# rotorsteuerung_create.net
KiCad netlist of a schematic drawn in EAGLE
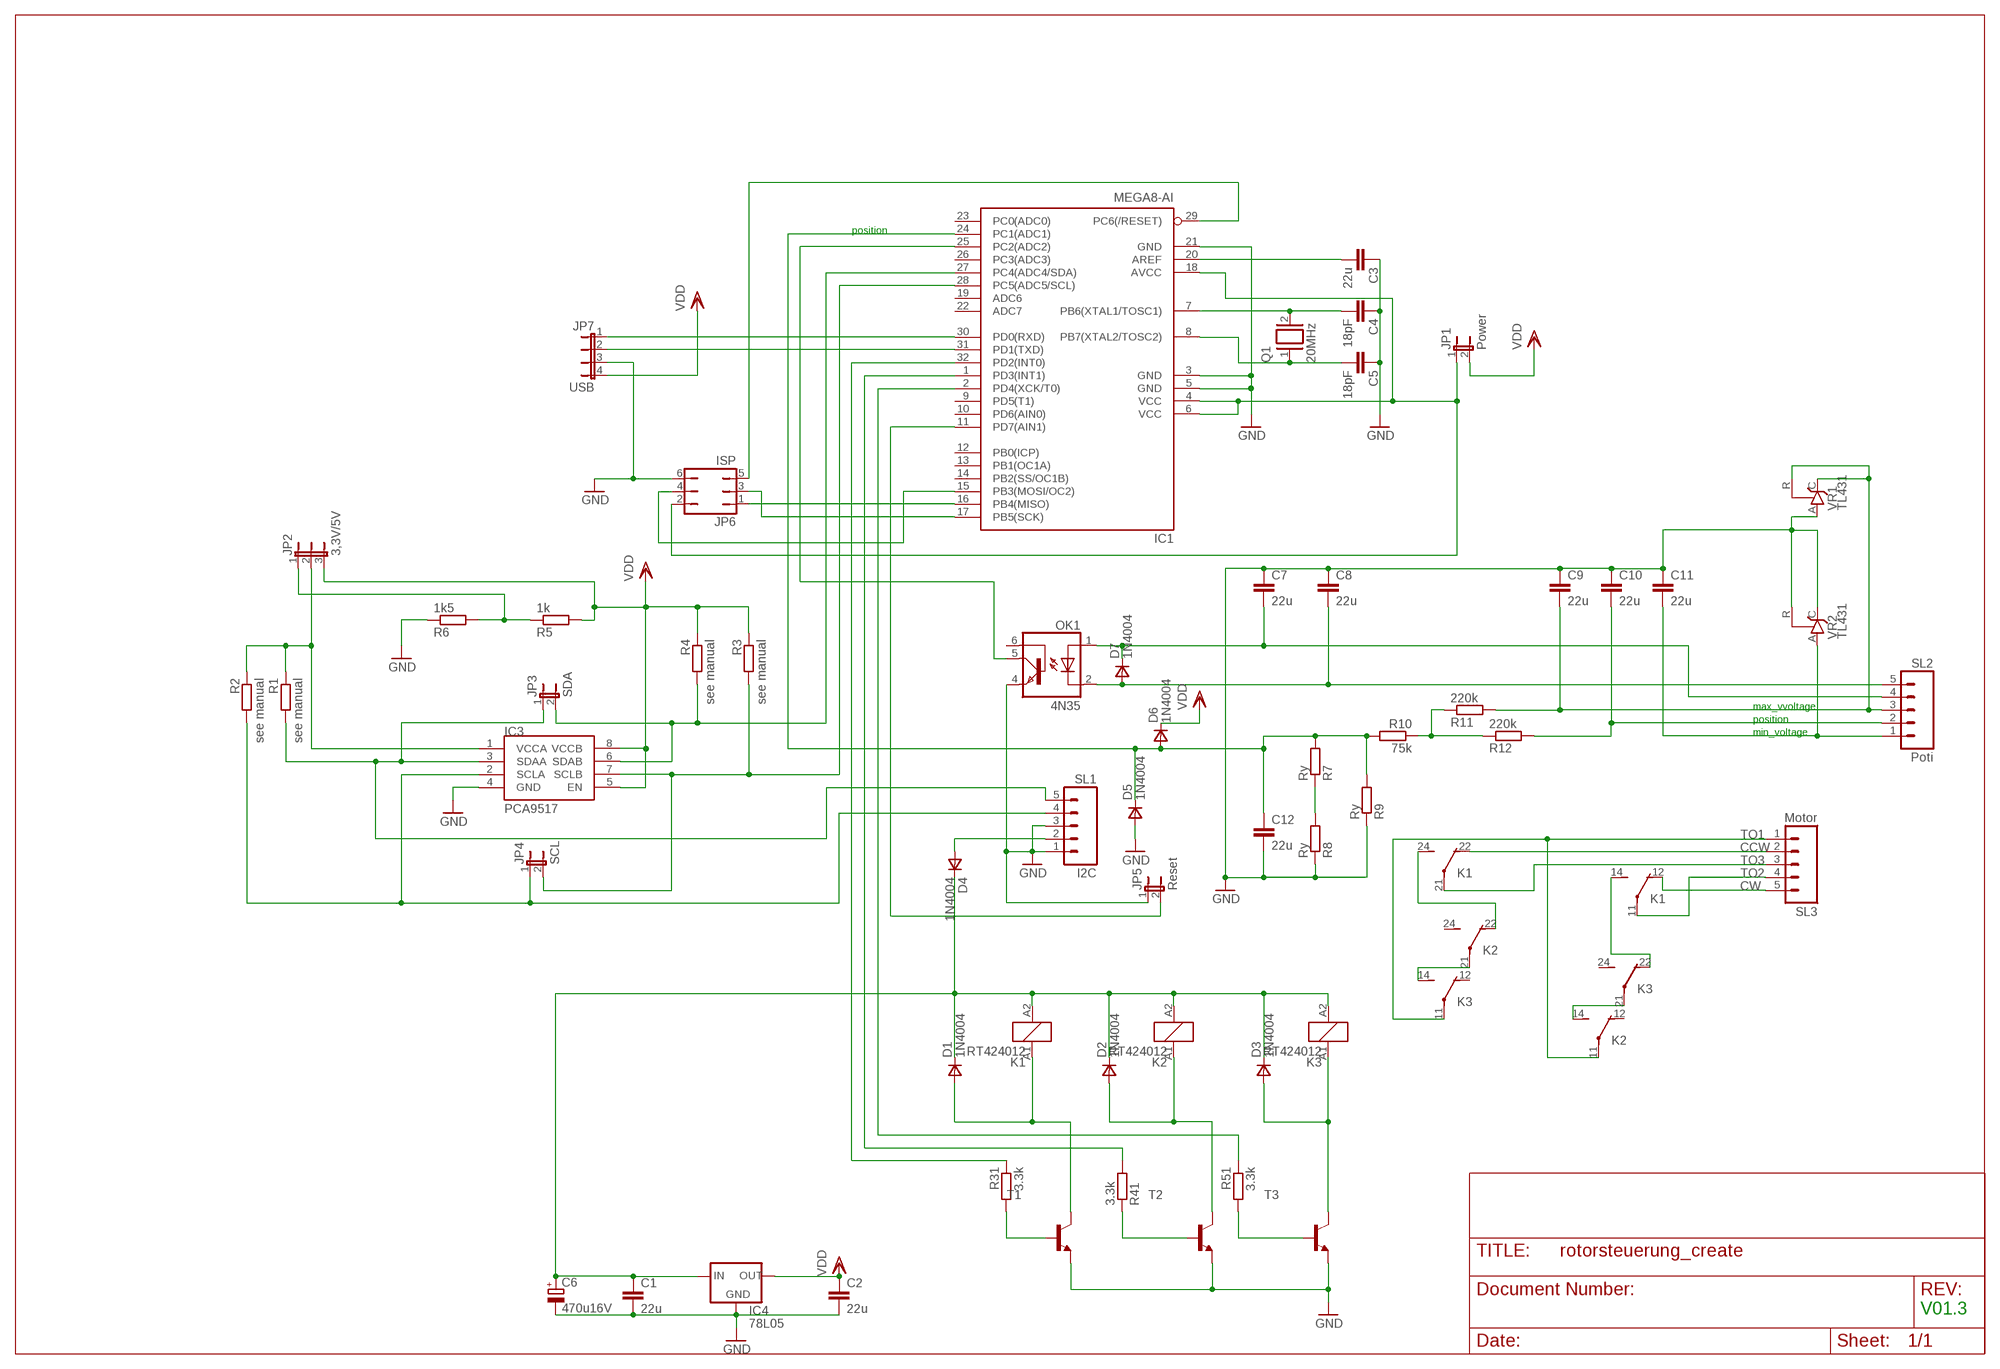
[diagram p0: schematic, sheet 1]

(export (version "E")
  (design (tool "Eeschema 10.0.6"))
  (components
    (comp (ref "C1")
      (value "22u")
      (footprint "eagle-import:C1206")
      (libsource (lib "eagle-import") (part "C-EUC1206"))
    )
    (comp (ref "C2")
      (value "22u")
      (footprint "eagle-import:C1206")
      (libsource (lib "eagle-import") (part "C-EUC1206"))
    )
    (comp (ref "C3")
      (value "22u")
      (footprint "eagle-import:C1206")
      (libsource (lib "eagle-import") (part "C-EUC1206"))
    )
    (comp (ref "C4")
      (value "18pF")
      (footprint "eagle-import:C025-024X044")
      (libsource (lib "eagle-import") (part "C-EU025-024X044"))
    )
    (comp (ref "C5")
      (value "18pF")
      (footprint "eagle-import:C025-024X044")
      (libsource (lib "eagle-import") (part "C-EU025-024X044"))
    )
    (comp (ref "C6")
      (value "470u16V")
      (footprint "eagle-import:E5-10,5")
      (libsource (lib "eagle-import") (part "CPOL-EUE5-10.5"))
    )
    (comp (ref "C7")
      (value "22u")
      (footprint "eagle-import:C1206")
      (libsource (lib "eagle-import") (part "C-EUC1206"))
    )
    (comp (ref "C8")
      (value "22u")
      (footprint "eagle-import:C1206")
      (libsource (lib "eagle-import") (part "C-EUC1206"))
    )
    (comp (ref "C9")
      (value "22u")
      (footprint "eagle-import:C1206")
      (libsource (lib "eagle-import") (part "C-EUC1206"))
    )
    (comp (ref "C10")
      (value "22u")
      (footprint "eagle-import:C1206")
      (libsource (lib "eagle-import") (part "C-EUC1206"))
    )
    (comp (ref "C11")
      (value "22u")
      (footprint "eagle-import:C1206")
      (libsource (lib "eagle-import") (part "C-EUC1206"))
    )
    (comp (ref "C12")
      (value "22u")
      (footprint "eagle-import:C1206")
      (libsource (lib "eagle-import") (part "C-EUC1206"))
    )
    (comp (ref "D1")
      (value "1N4004")
      (footprint "eagle-import:E2LINE")
      (libsource (lib "eagle-import") (part "D_E2L"))
    )
    (comp (ref "D2")
      (value "1N4004")
      (footprint "eagle-import:E2LINE")
      (libsource (lib "eagle-import") (part "D_E2L"))
    )
    (comp (ref "D3")
      (value "1N4004")
      (footprint "eagle-import:E2LINE")
      (libsource (lib "eagle-import") (part "D_E2L"))
    )
    (comp (ref "D4")
      (value "1N4004")
      (footprint "eagle-import:E2LINE")
      (libsource (lib "eagle-import") (part "D_E2L"))
    )
    (comp (ref "D5")
      (value "1N4004")
      (footprint "eagle-import:E2LINE")
      (libsource (lib "eagle-import") (part "D_E2L"))
    )
    (comp (ref "D6")
      (value "1N4004")
      (footprint "eagle-import:E2LINE")
      (libsource (lib "eagle-import") (part "D_E2L"))
    )
    (comp (ref "D7")
      (value "1N4004")
      (footprint "eagle-import:E2LINE")
      (libsource (lib "eagle-import") (part "D_E2L"))
    )
    (comp (ref "IC1")
      (value "MEGA8-AI")
      (footprint "eagle-import:TQFP32-08")
      (fields (field (name "MPN") "ATMEGA8-16AU"))
      (libsource (lib "eagle-import") (part "MEGA8-AI"))
    )
    (comp (ref "IC3")
      (value "PCA9517")
      (footprint "eagle-import:SO-08")
      (libsource (lib "eagle-import") (part "PCA9517"))
    )
    (comp (ref "IC4")
      (value "78L05")
      (footprint "eagle-import:78LXX")
      (libsource (lib "eagle-import") (part "78LXX"))
    )
    (comp (ref "JP1")
      (value "Power")
      (footprint "eagle-import:JP1")
      (libsource (lib "eagle-import") (part "JP1E"))
    )
    (comp (ref "JP2")
      (value "3,3V/5V")
      (footprint "eagle-import:JP2")
      (libsource (lib "eagle-import") (part "JP2E"))
    )
    (comp (ref "JP3")
      (value "SDA")
      (footprint "eagle-import:JP1")
      (libsource (lib "eagle-import") (part "JP1E"))
    )
    (comp (ref "JP4")
      (value "SCL")
      (footprint "eagle-import:JP1")
      (libsource (lib "eagle-import") (part "JP1E"))
    )
    (comp (ref "JP5")
      (value "Reset")
      (footprint "eagle-import:JP1")
      (libsource (lib "eagle-import") (part "JP1E"))
    )
    (comp (ref "JP6")
      (value "ISP")
      (footprint "eagle-import:JP3Q")
      (libsource (lib "eagle-import") (part "JP3Q"))
    )
    (comp (ref "JP7")
      (value "USB")
      (footprint "eagle-import:JP4")
      (libsource (lib "eagle-import") (part "JP4E"))
    )
    (comp (ref "K1")
      (value "RT424012")
      (footprint "eagle-import:RT2C_O")
      (libsource (lib "eagle-import") (part "RT42?4012"))
    )
    (comp (ref "K2")
      (value "RT424012")
      (footprint "eagle-import:RT2C_O")
      (libsource (lib "eagle-import") (part "RT42?4012"))
    )
    (comp (ref "K3")
      (value "RT424012")
      (footprint "eagle-import:RT2C_O")
      (libsource (lib "eagle-import") (part "RT42?4012"))
    )
    (comp (ref "OK1")
      (value "4N35")
      (footprint "eagle-import:DIL06")
      (libsource (lib "eagle-import") (part "4N35"))
    )
    (comp (ref "Q1")
      (value "20MHz")
      (footprint "eagle-import:QS")
      (libsource (lib "eagle-import") (part "XTAL/S"))
    )
    (comp (ref "R1")
      (value "see manual")
      (footprint "eagle-import:M1206")
      (libsource (lib "eagle-import") (part "resistor_R-EU_M1206"))
    )
    (comp (ref "R2")
      (value "see manual")
      (footprint "eagle-import:M1206")
      (libsource (lib "eagle-import") (part "resistor_R-EU_M1206"))
    )
    (comp (ref "R3")
      (value "see manual")
      (footprint "eagle-import:R1206")
      (libsource (lib "eagle-import") (part "resistor_R-EU_R1206"))
    )
    (comp (ref "R4")
      (value "see manual")
      (footprint "eagle-import:R1206")
      (libsource (lib "eagle-import") (part "resistor_R-EU_R1206"))
    )
    (comp (ref "R5")
      (value "1k")
      (footprint "eagle-import:R1206")
      (libsource (lib "eagle-import") (part "resistor_R-EU_R1206"))
    )
    (comp (ref "R6")
      (value "1k5")
      (footprint "eagle-import:R1206")
      (libsource (lib "eagle-import") (part "resistor_R-EU_R1206"))
    )
    (comp (ref "R7")
      (value "Ry")
      (footprint "eagle-import:0204_7")
      (libsource (lib "eagle-import") (part "R-EU_0204/7"))
    )
    (comp (ref "R8")
      (value "Ry")
      (footprint "eagle-import:0204_7")
      (libsource (lib "eagle-import") (part "R-EU_0204/7"))
    )
    (comp (ref "R9")
      (value "Ry")
      (footprint "eagle-import:0204_7")
      (libsource (lib "eagle-import") (part "R-EU_0204/7"))
    )
    (comp (ref "R10")
      (value "75k")
      (footprint "eagle-import:0204_7")
      (libsource (lib "eagle-import") (part "R-EU_0204/7"))
    )
    (comp (ref "R11")
      (value "220k")
      (footprint "eagle-import:0204_7")
      (libsource (lib "eagle-import") (part "R-EU_0204/7"))
    )
    (comp (ref "R12")
      (value "220k")
      (footprint "eagle-import:0204_7")
      (libsource (lib "eagle-import") (part "R-EU_0204/7"))
    )
    (comp (ref "R31")
      (value "3.3k")
      (footprint "eagle-import:R1206")
      (libsource (lib "eagle-import") (part "resistor_R-EU_R1206"))
    )
    (comp (ref "R41")
      (value "3.3k")
      (footprint "eagle-import:R1206")
      (libsource (lib "eagle-import") (part "resistor_R-EU_R1206"))
    )
    (comp (ref "R51")
      (value "3.3k")
      (footprint "eagle-import:R1206")
      (libsource (lib "eagle-import") (part "resistor_R-EU_R1206"))
    )
    (comp (ref "SL1")
      (value "I2C")
      (footprint "eagle-import:05P")
      (libsource (lib "eagle-import") (part "M05"))
    )
    (comp (ref "SL2")
      (value "Poti")
      (footprint "eagle-import:05P")
      (libsource (lib "eagle-import") (part "M05"))
    )
    (comp (ref "SL3")
      (value "Motor")
      (footprint "eagle-import:05P")
      (libsource (lib "eagle-import") (part "M05"))
    )
    (comp (ref "T1")
      (value "BC817-16-NPN-SOT23-BEC")
      (footprint "eagle-import:SOT23-BEC")
      (libsource (lib "eagle-import") (part "-NPN-SOT23-BECBC817-16"))
    )
    (comp (ref "T2")
      (value "BC817-16-NPN-SOT23-BEC")
      (footprint "eagle-import:SOT23-BEC")
      (libsource (lib "eagle-import") (part "-NPN-SOT23-BECBC817-16"))
    )
    (comp (ref "T3")
      (value "BC817-16-NPN-SOT23-BEC")
      (footprint "eagle-import:SOT23-BEC")
      (libsource (lib "eagle-import") (part "-NPN-SOT23-BECBC817-16"))
    )
    (comp (ref "VR1")
      (value "TL431")
      (footprint "eagle-import:TO92-CLP")
      (libsource (lib "eagle-import") (part "TL431CLP"))
    )
    (comp (ref "VR2")
      (value "TL431")
      (footprint "eagle-import:TO92-CLP")
      (libsource (lib "eagle-import") (part "TL431CLP"))
    )
  )
  (nets
    (net (code "1") (name "/CCW") (class "Default")
      (node (ref "K1") (pin "22") (pinfunction "O_22") (pintype "passive"))
      (node (ref "SL3") (pin "2") (pinfunction "2_2") (pintype "passive"))
    )
    (net (code "2") (name "/CW") (class "Default")
      (node (ref "K1") (pin "12") (pinfunction "O_12") (pintype "passive"))
      (node (ref "SL3") (pin "5") (pinfunction "5_5") (pintype "passive"))
    )
    (net (code "3") (name "/TO1") (class "Default")
      (node (ref "K2") (pin "11") (pinfunction "P_11") (pintype "passive"))
      (node (ref "K3") (pin "11") (pinfunction "P_11") (pintype "passive"))
      (node (ref "SL3") (pin "1") (pinfunction "1_1") (pintype "passive"))
    )
    (net (code "4") (name "/TO2") (class "Default")
      (node (ref "K1") (pin "11") (pinfunction "P_11") (pintype "passive"))
      (node (ref "SL3") (pin "4") (pinfunction "4_4") (pintype "passive"))
    )
    (net (code "5") (name "/TO3") (class "Default")
      (node (ref "K1") (pin "21") (pinfunction "P_21") (pintype "passive"))
      (node (ref "SL3") (pin "3") (pinfunction "3_3") (pintype "passive"))
    )
    (net (code "6") (name "GND") (class "Default")
      (node (ref "C1") (pin "2") (pinfunction "2_2") (pintype "passive"))
      (node (ref "C10") (pin "1") (pinfunction "1_1") (pintype "passive"))
      (node (ref "C11") (pin "1") (pinfunction "1_1") (pintype "passive"))
      (node (ref "C12") (pin "2") (pinfunction "2_2") (pintype "passive"))
      (node (ref "C2") (pin "2") (pinfunction "2_2") (pintype "passive"))
      (node (ref "C3") (pin "1") (pinfunction "1_1") (pintype "passive"))
      (node (ref "C4") (pin "1") (pinfunction "1_1") (pintype "passive"))
      (node (ref "C5") (pin "1") (pinfunction "1_1") (pintype "passive"))
      (node (ref "C6") (pin "-") (pinfunction "-_-") (pintype "passive"))
      (node (ref "C7") (pin "1") (pinfunction "1_1") (pintype "passive"))
      (node (ref "C8") (pin "1") (pinfunction "1_1") (pintype "passive"))
      (node (ref "C9") (pin "1") (pinfunction "1_1") (pintype "passive"))
      (node (ref "D5") (pin "2") (pinfunction "A_2") (pintype "passive"))
      (node (ref "IC1") (pin "21") (pinfunction "GND_21") (pintype "power_in"))
      (node (ref "IC1") (pin "3") (pinfunction "GND_3") (pintype "power_in"))
      (node (ref "IC1") (pin "5") (pinfunction "GND_5") (pintype "power_in"))
      (node (ref "IC3") (pin "4") (pinfunction "GND_4") (pintype "bidirectional"))
      (node (ref "IC4") (pin "GND") (pinfunction "GND_GND") (pintype "input"))
      (node (ref "JP5") (pin "1") (pinfunction "1_1") (pintype "passive"))
      (node (ref "JP6") (pin "6") (pinfunction "6_6") (pintype "passive"))
      (node (ref "JP7") (pin "3") (pinfunction "3_3") (pintype "passive"))
      (node (ref "OK1") (pin "4") (pinfunction "EMI_4") (pintype "passive"))
      (node (ref "R6") (pin "1") (pinfunction "1_1") (pintype "passive"))
      (node (ref "R8") (pin "1") (pinfunction "1_1") (pintype "passive"))
      (node (ref "R9") (pin "1") (pinfunction "1_1") (pintype "passive"))
      (node (ref "SL1") (pin "1") (pinfunction "1_1") (pintype "passive"))
      (node (ref "SL1") (pin "3") (pinfunction "3_3") (pintype "passive"))
      (node (ref "T1") (pin "E") (pinfunction "E_E") (pintype "passive"))
      (node (ref "T2") (pin "E") (pinfunction "E_E") (pintype "passive"))
      (node (ref "T3") (pin "E") (pinfunction "E_E") (pintype "passive"))
      (node (ref "VR1") (pin "A") (pinfunction "A_A") (pintype "passive"))
      (node (ref "VR2") (pin "C") (pinfunction "C_C") (pintype "passive"))
      (node (ref "VR2") (pin "R") (pinfunction "R_R") (pintype "passive"))
    )
    (net (code "7") (name "Net-(C9-Pad2)") (class "Default")
      (node (ref "C9") (pin "2") (pinfunction "2_2") (pintype "passive"))
      (node (ref "R11") (pin "2") (pinfunction "2_2") (pintype "passive"))
      (node (ref "SL2") (pin "3") (pinfunction "3_3") (pintype "passive"))
      (node (ref "VR1") (pin "C") (pinfunction "C_C") (pintype "passive"))
      (node (ref "VR1") (pin "R") (pinfunction "R_R") (pintype "passive"))
    )
    (net (code "8") (name "Net-(C10-Pad2)") (class "Default")
      (node (ref "C10") (pin "2") (pinfunction "2_2") (pintype "passive"))
      (node (ref "R12") (pin "2") (pinfunction "2_2") (pintype "passive"))
      (node (ref "SL2") (pin "2") (pinfunction "2_2") (pintype "passive"))
    )
    (net (code "9") (name "Net-(C11-Pad2)") (class "Default")
      (node (ref "C11") (pin "2") (pinfunction "2_2") (pintype "passive"))
      (node (ref "SL2") (pin "1") (pinfunction "1_1") (pintype "passive"))
      (node (ref "VR2") (pin "A") (pinfunction "A_A") (pintype "passive"))
    )
    (net (code "10") (name "Net-(D1-A)") (class "Default")
      (node (ref "D1") (pin "2") (pinfunction "A_2") (pintype "passive"))
      (node (ref "K1") (pin "A1") (pinfunction "1_A1") (pintype "passive"))
      (node (ref "T1") (pin "C") (pinfunction "C_C") (pintype "passive"))
    )
    (net (code "11") (name "Net-(D1-C)") (class "Default")
      (node (ref "C1") (pin "1") (pinfunction "1_1") (pintype "passive"))
      (node (ref "C6") (pin "+") (pinfunction "+_+") (pintype "passive"))
      (node (ref "D1") (pin "1") (pinfunction "C_1") (pintype "passive"))
      (node (ref "D2") (pin "1") (pinfunction "C_1") (pintype "passive"))
      (node (ref "D3") (pin "1") (pinfunction "C_1") (pintype "passive"))
      (node (ref "D4") (pin "1") (pinfunction "C_1") (pintype "passive"))
      (node (ref "IC4") (pin "IN") (pinfunction "IN_IN") (pintype "input"))
      (node (ref "K1") (pin "A2") (pinfunction "2_A2") (pintype "passive"))
      (node (ref "K2") (pin "A2") (pinfunction "2_A2") (pintype "passive"))
      (node (ref "K3") (pin "A2") (pinfunction "2_A2") (pintype "passive"))
    )
    (net (code "12") (name "Net-(D2-A)") (class "Default")
      (node (ref "D2") (pin "2") (pinfunction "A_2") (pintype "passive"))
      (node (ref "K2") (pin "A1") (pinfunction "1_A1") (pintype "passive"))
      (node (ref "T2") (pin "C") (pinfunction "C_C") (pintype "passive"))
    )
    (net (code "13") (name "Net-(D3-A)") (class "Default")
      (node (ref "D3") (pin "2") (pinfunction "A_2") (pintype "passive"))
      (node (ref "K3") (pin "A1") (pinfunction "1_A1") (pintype "passive"))
      (node (ref "T3") (pin "C") (pinfunction "C_C") (pintype "passive"))
    )
    (net (code "14") (name "Net-(D4-A)") (class "Default")
      (node (ref "D4") (pin "2") (pinfunction "A_2") (pintype "passive"))
      (node (ref "SL1") (pin "2") (pinfunction "2_2") (pintype "passive"))
    )
    (net (code "15") (name "Net-(D5-C)") (class "Default")
      (node (ref "C12") (pin "1") (pinfunction "1_1") (pintype "passive"))
      (node (ref "D5") (pin "1") (pinfunction "C_1") (pintype "passive"))
      (node (ref "D6") (pin "2") (pinfunction "A_2") (pintype "passive"))
      (node (ref "IC1") (pin "24") (pinfunction "PC1(ADC1)_24") (pintype "bidirectional"))
      (node (ref "R10") (pin "2") (pinfunction "2_2") (pintype "passive"))
      (node (ref "R7") (pin "2") (pinfunction "2_2") (pintype "passive"))
      (node (ref "R9") (pin "2") (pinfunction "2_2") (pintype "passive"))
    )
    (net (code "16") (name "Net-(D7-A)") (class "Default")
      (node (ref "C8") (pin "2") (pinfunction "2_2") (pintype "passive"))
      (node (ref "D7") (pin "2") (pinfunction "A_2") (pintype "passive"))
      (node (ref "OK1") (pin "2") (pinfunction "C_2") (pintype "passive"))
      (node (ref "SL2") (pin "5") (pinfunction "5_5") (pintype "passive"))
    )
    (net (code "17") (name "Net-(D7-C)") (class "Default")
      (node (ref "C7") (pin "2") (pinfunction "2_2") (pintype "passive"))
      (node (ref "D7") (pin "1") (pinfunction "C_1") (pintype "passive"))
      (node (ref "OK1") (pin "1") (pinfunction "A_1") (pintype "passive"))
      (node (ref "SL2") (pin "4") (pinfunction "4_4") (pintype "passive"))
    )
    (net (code "18") (name "Net-(IC1-AREF)") (class "Default")
      (node (ref "C3") (pin "2") (pinfunction "2_2") (pintype "passive"))
      (node (ref "IC1") (pin "20") (pinfunction "AREF_20") (pintype "passive"))
    )
    (net (code "19") (name "Net-(IC1-AVCC)") (class "Default")
      (node (ref "IC1") (pin "18") (pinfunction "AVCC_18") (pintype "power_in"))
      (node (ref "IC1") (pin "4") (pinfunction "VCC_4") (pintype "power_in"))
      (node (ref "IC1") (pin "6") (pinfunction "VCC_6") (pintype "power_in"))
      (node (ref "JP1") (pin "1") (pinfunction "1_1") (pintype "passive"))
      (node (ref "JP6") (pin "2") (pinfunction "2_2") (pintype "passive"))
    )
    (net (code "20") (name "Net-(IC1-PB3(MOSI{slash}OC2))") (class "Default")
      (node (ref "IC1") (pin "15") (pinfunction "PB3(MOSI/OC2)_15") (pintype "bidirectional"))
      (node (ref "JP6") (pin "4") (pinfunction "4_4") (pintype "passive"))
    )
    (net (code "21") (name "Net-(IC1-PB4(MISO))") (class "Default")
      (node (ref "IC1") (pin "16") (pinfunction "PB4(MISO)_16") (pintype "bidirectional"))
      (node (ref "JP6") (pin "1") (pinfunction "1_1") (pintype "passive"))
    )
    (net (code "22") (name "Net-(IC1-PB5(SCK))") (class "Default")
      (node (ref "IC1") (pin "17") (pinfunction "PB5(SCK)_17") (pintype "bidirectional"))
      (node (ref "JP6") (pin "3") (pinfunction "3_3") (pintype "passive"))
    )
    (net (code "23") (name "Net-(IC1-PB6(XTAL1{slash}TOSC1))") (class "Default")
      (node (ref "C4") (pin "2") (pinfunction "2_2") (pintype "passive"))
      (node (ref "IC1") (pin "7") (pinfunction "PB6(XTAL1/TOSC1)_7") (pintype "bidirectional"))
      (node (ref "Q1") (pin "2") (pinfunction "2_2") (pintype "passive"))
    )
    (net (code "24") (name "Net-(IC1-PB7(XTAL2{slash}TOSC2))") (class "Default")
      (node (ref "C5") (pin "2") (pinfunction "2_2") (pintype "passive"))
      (node (ref "IC1") (pin "8") (pinfunction "PB7(XTAL2/TOSC2)_8") (pintype "bidirectional"))
      (node (ref "Q1") (pin "1") (pinfunction "1_1") (pintype "passive"))
    )
    (net (code "25") (name "Net-(IC1-PC2(ADC2))") (class "Default")
      (node (ref "IC1") (pin "25") (pinfunction "PC2(ADC2)_25") (pintype "bidirectional"))
      (node (ref "OK1") (pin "5") (pinfunction "COL_5") (pintype "passive"))
    )
    (net (code "26") (name "Net-(IC1-PC4(ADC4{slash}SDA))") (class "Default")
      (node (ref "IC1") (pin "27") (pinfunction "PC4(ADC4/SDA)_27") (pintype "bidirectional"))
      (node (ref "IC3") (pin "6") (pinfunction "SDAB_6") (pintype "bidirectional"))
      (node (ref "JP3") (pin "2") (pinfunction "2_2") (pintype "passive"))
      (node (ref "R4") (pin "2") (pinfunction "2_2") (pintype "passive"))
    )
    (net (code "27") (name "Net-(IC1-PC5(ADC5{slash}SCL))") (class "Default")
      (node (ref "IC1") (pin "28") (pinfunction "PC5(ADC5/SCL)_28") (pintype "bidirectional"))
      (node (ref "IC3") (pin "7") (pinfunction "SCLB_7") (pintype "bidirectional"))
      (node (ref "JP4") (pin "2") (pinfunction "2_2") (pintype "passive"))
      (node (ref "R3") (pin "2") (pinfunction "2_2") (pintype "passive"))
    )
    (net (code "28") (name "Net-(IC1-PC6({slash}RESET))") (class "Default")
      (node (ref "IC1") (pin "29") (pinfunction "PC6(/RESET)_29") (pintype "bidirectional"))
      (node (ref "JP6") (pin "5") (pinfunction "5_5") (pintype "passive"))
    )
    (net (code "29") (name "Net-(IC1-PD0(RXD))") (class "Default")
      (node (ref "IC1") (pin "30") (pinfunction "PD0(RXD)_30") (pintype "bidirectional"))
      (node (ref "JP7") (pin "1") (pinfunction "1_1") (pintype "passive"))
    )
    (net (code "30") (name "Net-(IC1-PD1(TXD))") (class "Default")
      (node (ref "IC1") (pin "31") (pinfunction "PD1(TXD)_31") (pintype "bidirectional"))
      (node (ref "JP7") (pin "2") (pinfunction "2_2") (pintype "passive"))
    )
    (net (code "31") (name "Net-(IC1-PD2(INT0))") (class "Default")
      (node (ref "IC1") (pin "32") (pinfunction "PD2(INT0)_32") (pintype "bidirectional"))
      (node (ref "R31") (pin "1") (pinfunction "1_1") (pintype "passive"))
    )
    (net (code "32") (name "Net-(IC1-PD3(INT1))") (class "Default")
      (node (ref "IC1") (pin "1") (pinfunction "PD3(INT1)_1") (pintype "bidirectional"))
      (node (ref "R41") (pin "2") (pinfunction "2_2") (pintype "passive"))
    )
    (net (code "33") (name "Net-(IC1-PD4(XCK{slash}T0))") (class "Default")
      (node (ref "IC1") (pin "2") (pinfunction "PD4(XCK/T0)_2") (pintype "bidirectional"))
      (node (ref "R51") (pin "1") (pinfunction "1_1") (pintype "passive"))
    )
    (net (code "34") (name "Net-(IC1-PD7(AIN1))") (class "Default")
      (node (ref "IC1") (pin "11") (pinfunction "PD7(AIN1)_11") (pintype "bidirectional"))
      (node (ref "JP5") (pin "2") (pinfunction "2_2") (pintype "passive"))
    )
    (net (code "35") (name "Net-(IC3-SCLA)") (class "Default")
      (node (ref "IC3") (pin "2") (pinfunction "SCLA_2") (pintype "bidirectional"))
      (node (ref "JP4") (pin "1") (pinfunction "1_1") (pintype "passive"))
      (node (ref "R2") (pin "2") (pinfunction "2_2") (pintype "passive"))
      (node (ref "SL1") (pin "4") (pinfunction "4_4") (pintype "passive"))
    )
    (net (code "36") (name "Net-(IC3-SDAA)") (class "Default")
      (node (ref "IC3") (pin "3") (pinfunction "SDAA_3") (pintype "bidirectional"))
      (node (ref "JP3") (pin "1") (pinfunction "1_1") (pintype "passive"))
      (node (ref "R1") (pin "2") (pinfunction "2_2") (pintype "passive"))
      (node (ref "SL1") (pin "5") (pinfunction "5_5") (pintype "passive"))
    )
    (net (code "37") (name "Net-(IC3-VCCA)") (class "Default")
      (node (ref "IC3") (pin "1") (pinfunction "VCCA_1") (pintype "bidirectional"))
      (node (ref "JP2") (pin "2") (pinfunction "2_2") (pintype "passive"))
      (node (ref "R1") (pin "1") (pinfunction "1_1") (pintype "passive"))
      (node (ref "R2") (pin "1") (pinfunction "1_1") (pintype "passive"))
    )
    (net (code "38") (name "Net-(JP2-Pad1)") (class "Default")
      (node (ref "JP2") (pin "1") (pinfunction "1_1") (pintype "passive"))
      (node (ref "R5") (pin "1") (pinfunction "1_1") (pintype "passive"))
      (node (ref "R6") (pin "2") (pinfunction "2_2") (pintype "passive"))
    )
    (net (code "39") (name "Net-(K1B-S)") (class "Default")
      (node (ref "K1") (pin "14") (pinfunction "S_14") (pintype "passive"))
      (node (ref "K3") (pin "22") (pinfunction "O_22") (pintype "passive"))
    )
    (net (code "40") (name "Net-(K1C-S)") (class "Default")
      (node (ref "K1") (pin "24") (pinfunction "S_24") (pintype "passive"))
      (node (ref "K2") (pin "22") (pinfunction "O_22") (pintype "passive"))
    )
    (net (code "41") (name "Net-(K2B-S)") (class "Default")
      (node (ref "K2") (pin "14") (pinfunction "S_14") (pintype "passive"))
      (node (ref "K3") (pin "21") (pinfunction "P_21") (pintype "passive"))
    )
    (net (code "42") (name "Net-(K2C-P)") (class "Default")
      (node (ref "K2") (pin "21") (pinfunction "P_21") (pintype "passive"))
      (node (ref "K3") (pin "14") (pinfunction "S_14") (pintype "passive"))
    )
    (net (code "43") (name "Net-(R7-Pad1)") (class "Default")
      (node (ref "R7") (pin "1") (pinfunction "1_1") (pintype "passive"))
      (node (ref "R8") (pin "2") (pinfunction "2_2") (pintype "passive"))
    )
    (net (code "44") (name "Net-(R10-Pad1)") (class "Default")
      (node (ref "R10") (pin "1") (pinfunction "1_1") (pintype "passive"))
      (node (ref "R11") (pin "1") (pinfunction "1_1") (pintype "passive"))
      (node (ref "R12") (pin "1") (pinfunction "1_1") (pintype "passive"))
    )
    (net (code "45") (name "Net-(R31-Pad2)") (class "Default")
      (node (ref "R31") (pin "2") (pinfunction "2_2") (pintype "passive"))
      (node (ref "T1") (pin "B") (pinfunction "B_B") (pintype "passive"))
    )
    (net (code "46") (name "Net-(R41-Pad1)") (class "Default")
      (node (ref "R41") (pin "1") (pinfunction "1_1") (pintype "passive"))
      (node (ref "T2") (pin "B") (pinfunction "B_B") (pintype "passive"))
    )
    (net (code "47") (name "Net-(R51-Pad2)") (class "Default")
      (node (ref "R51") (pin "2") (pinfunction "2_2") (pintype "passive"))
      (node (ref "T3") (pin "B") (pinfunction "B_B") (pintype "passive"))
    )
    (net (code "48") (name "VDD") (class "Default")
      (node (ref "C2") (pin "1") (pinfunction "1_1") (pintype "passive"))
      (node (ref "D6") (pin "1") (pinfunction "C_1") (pintype "passive"))
      (node (ref "IC3") (pin "5") (pinfunction "EN_5") (pintype "bidirectional"))
      (node (ref "IC3") (pin "8") (pinfunction "VCCB_8") (pintype "bidirectional"))
      (node (ref "IC4") (pin "OUT") (pinfunction "OUT_OUT") (pintype "passive"))
      (node (ref "JP1") (pin "2") (pinfunction "2_2") (pintype "passive"))
      (node (ref "JP2") (pin "3") (pinfunction "3_3") (pintype "passive"))
      (node (ref "JP7") (pin "4") (pinfunction "4_4") (pintype "passive"))
      (node (ref "R3") (pin "1") (pinfunction "1_1") (pintype "passive"))
      (node (ref "R4") (pin "1") (pinfunction "1_1") (pintype "passive"))
      (node (ref "R5") (pin "2") (pinfunction "2_2") (pintype "passive"))
    )
    (net (code "49") (name "unconnected-(IC1-ADC6-Pad19)") (class "Default")
      (node (ref "IC1") (pin "19") (pinfunction "ADC6_19") (pintype "bidirectional"))
    )
    (net (code "50") (name "unconnected-(IC1-ADC7-Pad22)") (class "Default")
      (node (ref "IC1") (pin "22") (pinfunction "ADC7_22") (pintype "bidirectional"))
    )
    (net (code "51") (name "unconnected-(IC1-PB0(ICP)-Pad12)") (class "Default")
      (node (ref "IC1") (pin "12") (pinfunction "PB0(ICP)_12") (pintype "bidirectional"))
    )
    (net (code "52") (name "unconnected-(IC1-PB1(OC1A)-Pad13)") (class "Default")
      (node (ref "IC1") (pin "13") (pinfunction "PB1(OC1A)_13") (pintype "bidirectional"))
    )
    (net (code "53") (name "unconnected-(IC1-PB2(SS{slash}OC1B)-Pad14)") (class "Default")
      (node (ref "IC1") (pin "14") (pinfunction "PB2(SS/OC1B)_14") (pintype "bidirectional"))
    )
    (net (code "54") (name "unconnected-(IC1-PC0(ADC0)-Pad23)") (class "Default")
      (node (ref "IC1") (pin "23") (pinfunction "PC0(ADC0)_23") (pintype "bidirectional"))
    )
    (net (code "55") (name "unconnected-(IC1-PC3(ADC3)-Pad26)") (class "Default")
      (node (ref "IC1") (pin "26") (pinfunction "PC3(ADC3)_26") (pintype "bidirectional"))
    )
    (net (code "56") (name "unconnected-(IC1-PD5(T1)-Pad9)") (class "Default")
      (node (ref "IC1") (pin "9") (pinfunction "PD5(T1)_9") (pintype "bidirectional"))
    )
    (net (code "57") (name "unconnected-(IC1-PD6(AIN0)-Pad10)") (class "Default")
      (node (ref "IC1") (pin "10") (pinfunction "PD6(AIN0)_10") (pintype "bidirectional"))
    )
    (net (code "58") (name "unconnected-(K2B-O-Pad12)") (class "Default")
      (node (ref "K2") (pin "12") (pinfunction "O_12") (pintype "passive"))
    )
    (net (code "59") (name "unconnected-(K2C-S-Pad24)") (class "Default")
      (node (ref "K2") (pin "24") (pinfunction "S_24") (pintype "passive"))
    )
    (net (code "60") (name "unconnected-(K3B-O-Pad12)") (class "Default")
      (node (ref "K3") (pin "12") (pinfunction "O_12") (pintype "passive"))
    )
    (net (code "61") (name "unconnected-(K3C-S-Pad24)") (class "Default")
      (node (ref "K3") (pin "24") (pinfunction "S_24") (pintype "passive"))
    )
    (net (code "62") (name "unconnected-(OK1-BAS-Pad6)") (class "Default")
      (node (ref "OK1") (pin "6") (pinfunction "BAS_6") (pintype "passive"))
    )
  )
)
